# ADC_Arduino_Uno_Shield.net
KiCad netlist of a schematic drawn in EAGLE
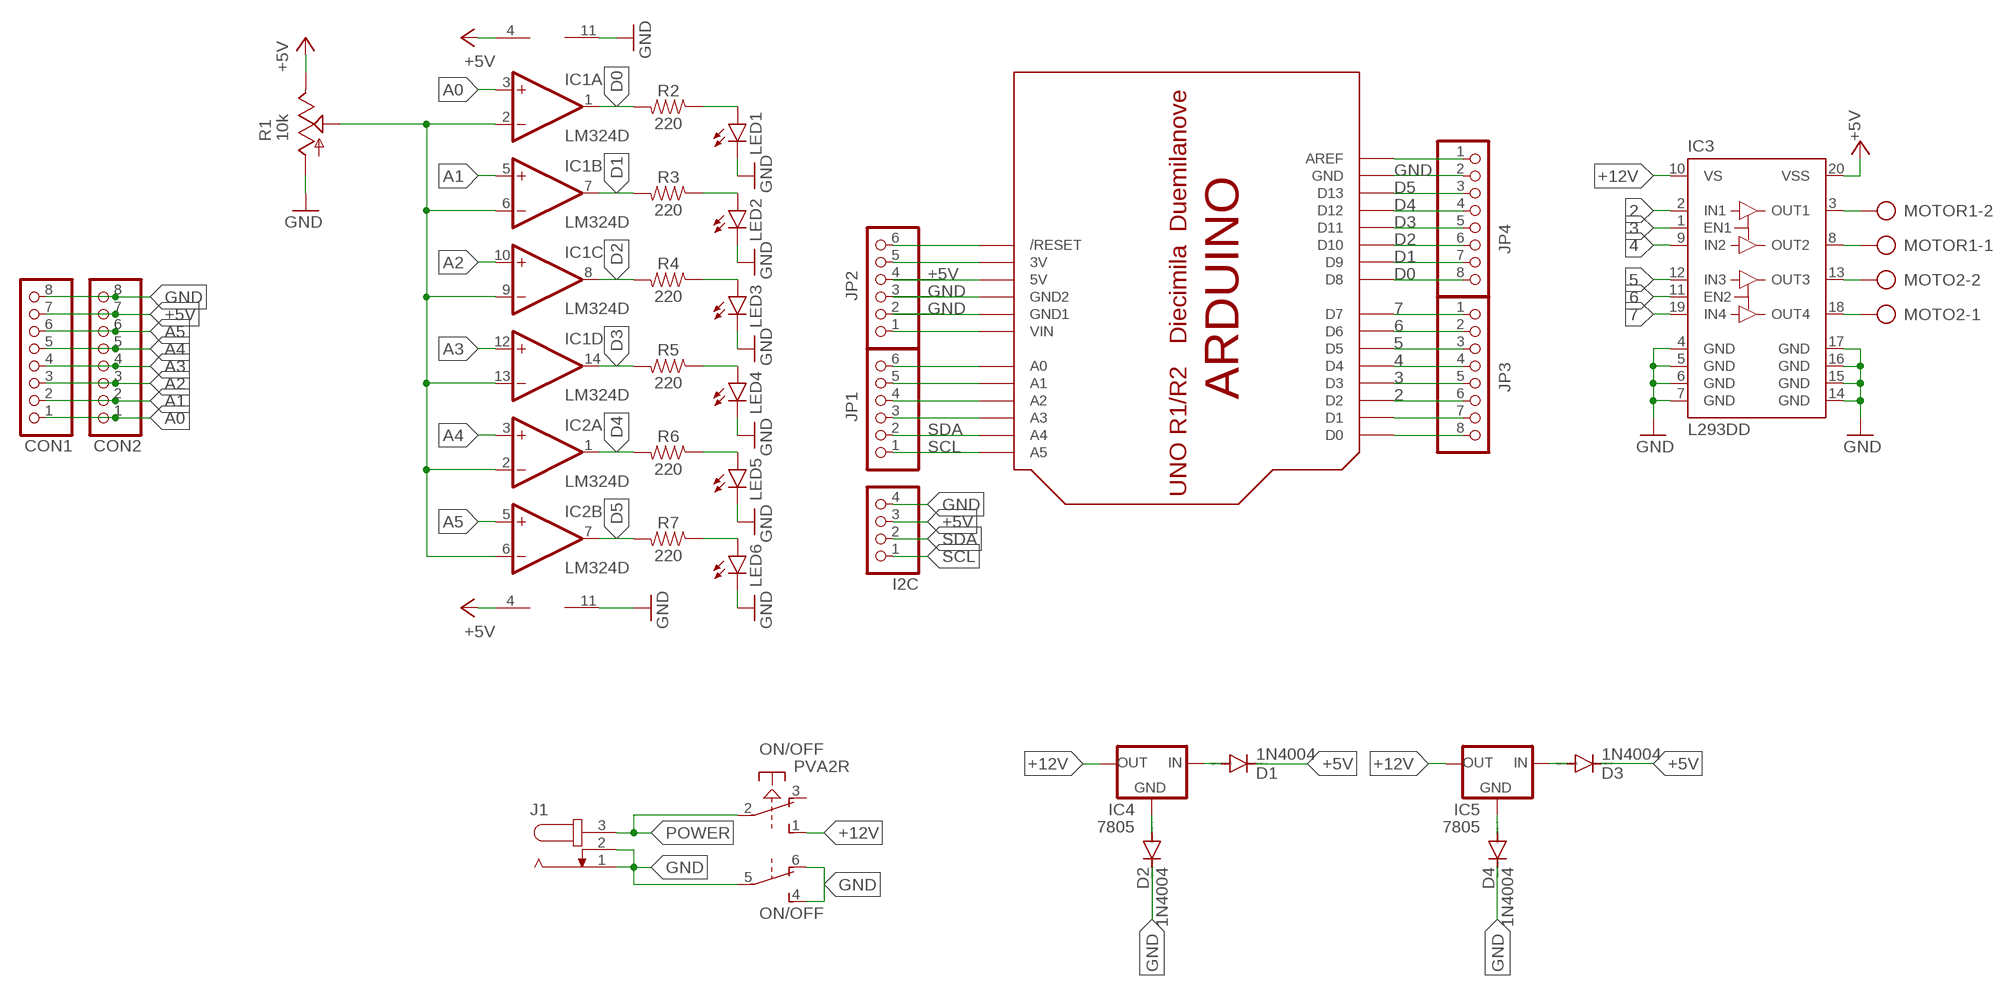
[diagram p0: schematic, sheet 1]

(export (version "E")
  (design (tool "Eeschema 10.0.6"))
  (components
    (comp (ref "CON1")
      (value "PINHD-1X8")
      (footprint "eagle-import:1X08")
      (libsource (lib "eagle-import") (part "PINHD-1X8"))
    )
    (comp (ref "CON2")
      (value "PINHD-1X8")
      (footprint "eagle-import:1X08")
      (libsource (lib "eagle-import") (part "PINHD-1X8"))
    )
    (comp (ref "D1")
      (value "1N4004")
      (footprint "eagle-import:DO41-10")
      (libsource (lib "eagle-import") (part "1N4004"))
    )
    (comp (ref "D2")
      (value "1N4004")
      (footprint "eagle-import:DO41-10")
      (libsource (lib "eagle-import") (part "1N4004"))
    )
    (comp (ref "D3")
      (value "1N4004")
      (footprint "eagle-import:DO41-10")
      (libsource (lib "eagle-import") (part "1N4004"))
    )
    (comp (ref "D4")
      (value "1N4004")
      (footprint "eagle-import:DO41-10")
      (libsource (lib "eagle-import") (part "1N4004"))
    )
    (comp (ref "I2C")
      (value "PINHD-1X4")
      (footprint "eagle-import:1X04")
      (libsource (lib "eagle-import") (part "PINHD-1X4"))
    )
    (comp (ref "IC1")
      (value "LM324D")
      (footprint "eagle-import:SO14")
      (libsource (lib "eagle-import") (part "LM324D"))
    )
    (comp (ref "IC2")
      (value "LM324D")
      (footprint "eagle-import:SO14")
      (libsource (lib "eagle-import") (part "LM324D"))
    )
    (comp (ref "IC3")
      (value "L293DD")
      (footprint "eagle-import:SO20")
      (libsource (lib "eagle-import") (part "L293DD"))
    )
    (comp (ref "IC4")
      (value "7805")
      (footprint "eagle-import:78XXS")
      (libsource (lib "eagle-import") (part "78XXS"))
    )
    (comp (ref "IC5")
      (value "7805")
      (footprint "eagle-import:78XXS")
      (libsource (lib "eagle-import") (part "78XXS"))
    )
    (comp (ref "J1")
      (value "JACK-PLUG0")
      (footprint "eagle-import:SPC4077")
      (libsource (lib "eagle-import") (part "JACK-PLUG0"))
    )
    (comp (ref "JP1")
      (value "PINHD-1X6")
      (footprint "eagle-import:1X06")
      (libsource (lib "eagle-import") (part "PINHD-1X6"))
    )
    (comp (ref "JP2")
      (value "PINHD-1X6")
      (footprint "eagle-import:1X06")
      (libsource (lib "eagle-import") (part "PINHD-1X6"))
    )
    (comp (ref "JP3")
      (value "PINHD-1X8")
      (footprint "eagle-import:1X08")
      (libsource (lib "eagle-import") (part "pinhead_325_PINHD-1X8"))
    )
    (comp (ref "JP4")
      (value "PINHD-1X8")
      (footprint "eagle-import:1X08")
      (libsource (lib "eagle-import") (part "pinhead_325_PINHD-1X8"))
    )
    (comp (ref "LED1")
      (value "LEDSML0805")
      (footprint "eagle-import:SML0805")
      (libsource (lib "eagle-import") (part "LEDSML0805"))
    )
    (comp (ref "LED2")
      (value "LEDSML0805")
      (footprint "eagle-import:SML0805")
      (libsource (lib "eagle-import") (part "LEDSML0805"))
    )
    (comp (ref "LED3")
      (value "LEDSML0805")
      (footprint "eagle-import:SML0805")
      (libsource (lib "eagle-import") (part "LEDSML0805"))
    )
    (comp (ref "LED4")
      (value "LEDSML0805")
      (footprint "eagle-import:SML0805")
      (libsource (lib "eagle-import") (part "LEDSML0805"))
    )
    (comp (ref "LED5")
      (value "LEDSML0805")
      (footprint "eagle-import:SML0805")
      (libsource (lib "eagle-import") (part "LEDSML0805"))
    )
    (comp (ref "LED6")
      (value "LEDSML0805")
      (footprint "eagle-import:SML0805")
      (libsource (lib "eagle-import") (part "LEDSML0805"))
    )
    (comp (ref "MOTO2")
      (value "AK500/2-H")
      (footprint "eagle-import:AK500_2-H")
      (libsource (lib "eagle-import") (part "AK500/2-H"))
    )
    (comp (ref "MOTOR1")
      (value "AK500/2-H")
      (footprint "eagle-import:AK500_2-H")
      (libsource (lib "eagle-import") (part "AK500/2-H"))
    )
    (comp (ref "ON/OFF")
      (value "PVA2R")
      (footprint "eagle-import:PVA2R")
      (libsource (lib "eagle-import") (part "PVA2R"))
    )
    (comp (ref "R1")
      (value "10k")
      (footprint "eagle-import:CA9V")
      (libsource (lib "eagle-import") (part "TRIM_US-CA9V"))
    )
    (comp (ref "R2")
      (value "220")
      (footprint "eagle-import:1206")
      (libsource (lib "eagle-import") (part "RESISTOR1206"))
    )
    (comp (ref "R3")
      (value "220")
      (footprint "eagle-import:1206")
      (libsource (lib "eagle-import") (part "RESISTOR1206"))
    )
    (comp (ref "R4")
      (value "220")
      (footprint "eagle-import:1206")
      (libsource (lib "eagle-import") (part "RESISTOR1206"))
    )
    (comp (ref "R5")
      (value "220")
      (footprint "eagle-import:1206")
      (libsource (lib "eagle-import") (part "RESISTOR1206"))
    )
    (comp (ref "R6")
      (value "220")
      (footprint "eagle-import:1206")
      (libsource (lib "eagle-import") (part "RESISTOR1206"))
    )
    (comp (ref "R7")
      (value "220")
      (footprint "eagle-import:1206")
      (libsource (lib "eagle-import") (part "RESISTOR1206"))
    )
    (comp (ref "U$2")
      (value "ARDUINO-NODIM")
      (footprint "eagle-import:ARDUINO-NODIM")
      (libsource (lib "eagle-import") (part "ARDUINO-NODIM"))
    )
  )
  (nets
    (net (code "1") (name "+5V") (class "Default")
      (node (ref "CON1") (pin "7") (pinfunction "7_7") (pintype "passive"))
      (node (ref "CON2") (pin "7") (pinfunction "7_7") (pintype "passive"))
      (node (ref "D1") (pin "C") (pinfunction "C_C") (pintype "passive"))
      (node (ref "D3") (pin "C") (pinfunction "C_C") (pintype "passive"))
      (node (ref "I2C") (pin "3") (pinfunction "3_3") (pintype "passive"))
      (node (ref "IC1") (pin "4") (pinfunction "V+_4") (pintype "power_in"))
      (node (ref "IC2") (pin "4") (pinfunction "V+_4") (pintype "power_in"))
      (node (ref "IC3") (pin "20") (pinfunction "VSS_20") (pintype "power_in"))
      (node (ref "JP2") (pin "4") (pinfunction "4_4") (pintype "passive"))
      (node (ref "R1") (pin "E") (pinfunction "E_E") (pintype "passive"))
      (node (ref "U$2") (pin "5V") (pinfunction "5V_5V") (pintype "power_in"))
    )
    (net (code "2") (name "+12V") (class "Default")
      (node (ref "IC3") (pin "10") (pinfunction "VS_10") (pintype "power_in"))
      (node (ref "IC4") (pin "OUT") (pinfunction "OUT_OUT") (pintype "passive"))
      (node (ref "IC5") (pin "OUT") (pinfunction "OUT_OUT") (pintype "passive"))
      (node (ref "ON/OFF") (pin "1") (pinfunction "S_1") (pintype "passive"))
    )
    (net (code "3") (name "2") (class "Default")
      (node (ref "IC3") (pin "2") (pinfunction "IN1_2") (pintype "input"))
      (node (ref "JP3") (pin "6") (pinfunction "6_6") (pintype "passive"))
      (node (ref "U$2") (pin "D2") (pinfunction "D2_D2") (pintype "bidirectional"))
    )
    (net (code "4") (name "3") (class "Default")
      (node (ref "IC3") (pin "1") (pinfunction "EN1_1") (pintype "input"))
      (node (ref "JP3") (pin "5") (pinfunction "5_5") (pintype "passive"))
      (node (ref "U$2") (pin "D3") (pinfunction "D3_D3") (pintype "bidirectional"))
    )
    (net (code "5") (name "4") (class "Default")
      (node (ref "IC3") (pin "9") (pinfunction "IN2_9") (pintype "input"))
      (node (ref "JP3") (pin "4") (pinfunction "4_4") (pintype "passive"))
      (node (ref "U$2") (pin "D4") (pinfunction "D4_D4") (pintype "bidirectional"))
    )
    (net (code "6") (name "5") (class "Default")
      (node (ref "IC3") (pin "12") (pinfunction "IN3_12") (pintype "input"))
      (node (ref "JP3") (pin "3") (pinfunction "3_3") (pintype "passive"))
      (node (ref "U$2") (pin "D5") (pinfunction "D5_D5") (pintype "bidirectional"))
    )
    (net (code "7") (name "6") (class "Default")
      (node (ref "IC3") (pin "11") (pinfunction "EN2_11") (pintype "input"))
      (node (ref "JP3") (pin "2") (pinfunction "2_2") (pintype "passive"))
      (node (ref "U$2") (pin "D6") (pinfunction "D6_D6") (pintype "bidirectional"))
    )
    (net (code "8") (name "7") (class "Default")
      (node (ref "IC3") (pin "19") (pinfunction "IN4_19") (pintype "input"))
      (node (ref "JP3") (pin "1") (pinfunction "1_1") (pintype "passive"))
      (node (ref "U$2") (pin "D7") (pinfunction "D7_D7") (pintype "bidirectional"))
    )
    (net (code "9") (name "A0") (class "Default")
      (node (ref "CON1") (pin "1") (pinfunction "1_1") (pintype "passive"))
      (node (ref "CON2") (pin "1") (pinfunction "1_1") (pintype "passive"))
      (node (ref "IC1") (pin "3") (pinfunction "+IN_3") (pintype "input"))
    )
    (net (code "10") (name "A1") (class "Default")
      (node (ref "CON1") (pin "2") (pinfunction "2_2") (pintype "passive"))
      (node (ref "CON2") (pin "2") (pinfunction "2_2") (pintype "passive"))
      (node (ref "IC1") (pin "5") (pinfunction "+IN_5") (pintype "input"))
    )
    (net (code "11") (name "A2") (class "Default")
      (node (ref "CON1") (pin "3") (pinfunction "3_3") (pintype "passive"))
      (node (ref "CON2") (pin "3") (pinfunction "3_3") (pintype "passive"))
      (node (ref "IC1") (pin "10") (pinfunction "+IN_10") (pintype "input"))
    )
    (net (code "12") (name "A3") (class "Default")
      (node (ref "CON1") (pin "4") (pinfunction "4_4") (pintype "passive"))
      (node (ref "CON2") (pin "4") (pinfunction "4_4") (pintype "passive"))
      (node (ref "IC1") (pin "12") (pinfunction "+IN_12") (pintype "input"))
    )
    (net (code "13") (name "A4") (class "Default")
      (node (ref "CON1") (pin "5") (pinfunction "5_5") (pintype "passive"))
      (node (ref "CON2") (pin "5") (pinfunction "5_5") (pintype "passive"))
      (node (ref "IC2") (pin "3") (pinfunction "+IN_3") (pintype "input"))
    )
    (net (code "14") (name "A5") (class "Default")
      (node (ref "CON1") (pin "6") (pinfunction "6_6") (pintype "passive"))
      (node (ref "CON2") (pin "6") (pinfunction "6_6") (pintype "passive"))
      (node (ref "IC2") (pin "5") (pinfunction "+IN_5") (pintype "input"))
    )
    (net (code "15") (name "D0") (class "Default")
      (node (ref "IC1") (pin "1") (pinfunction "OUT_1") (pintype "output"))
      (node (ref "JP4") (pin "8") (pinfunction "8_8") (pintype "passive"))
      (node (ref "R2") (pin "2") (pinfunction "2_2") (pintype "passive"))
      (node (ref "U$2") (pin "D8") (pinfunction "D8_D8") (pintype "bidirectional"))
    )
    (net (code "16") (name "D1") (class "Default")
      (node (ref "IC1") (pin "7") (pinfunction "OUT_7") (pintype "output"))
      (node (ref "JP4") (pin "7") (pinfunction "7_7") (pintype "passive"))
      (node (ref "R3") (pin "2") (pinfunction "2_2") (pintype "passive"))
      (node (ref "U$2") (pin "D9") (pinfunction "D9_D9") (pintype "bidirectional"))
    )
    (net (code "17") (name "D2") (class "Default")
      (node (ref "IC1") (pin "8") (pinfunction "OUT_8") (pintype "output"))
      (node (ref "JP4") (pin "6") (pinfunction "6_6") (pintype "passive"))
      (node (ref "R4") (pin "2") (pinfunction "2_2") (pintype "passive"))
      (node (ref "U$2") (pin "D10") (pinfunction "D10_D10") (pintype "bidirectional"))
    )
    (net (code "18") (name "D3") (class "Default")
      (node (ref "IC1") (pin "14") (pinfunction "OUT_14") (pintype "output"))
      (node (ref "JP4") (pin "5") (pinfunction "5_5") (pintype "passive"))
      (node (ref "R5") (pin "2") (pinfunction "2_2") (pintype "passive"))
      (node (ref "U$2") (pin "D11") (pinfunction "D11_D11") (pintype "bidirectional"))
    )
    (net (code "19") (name "D4") (class "Default")
      (node (ref "IC2") (pin "1") (pinfunction "OUT_1") (pintype "output"))
      (node (ref "JP4") (pin "4") (pinfunction "4_4") (pintype "passive"))
      (node (ref "R6") (pin "2") (pinfunction "2_2") (pintype "passive"))
      (node (ref "U$2") (pin "D12") (pinfunction "D12_D12") (pintype "bidirectional"))
    )
    (net (code "20") (name "D5") (class "Default")
      (node (ref "IC2") (pin "7") (pinfunction "OUT_7") (pintype "output"))
      (node (ref "JP4") (pin "3") (pinfunction "3_3") (pintype "passive"))
      (node (ref "R7") (pin "2") (pinfunction "2_2") (pintype "passive"))
      (node (ref "U$2") (pin "D13") (pinfunction "D13_D13") (pintype "bidirectional"))
    )
    (net (code "21") (name "GND") (class "Default")
      (node (ref "CON1") (pin "8") (pinfunction "8_8") (pintype "passive"))
      (node (ref "CON2") (pin "8") (pinfunction "8_8") (pintype "passive"))
      (node (ref "D2") (pin "C") (pinfunction "C_C") (pintype "passive"))
      (node (ref "D4") (pin "C") (pinfunction "C_C") (pintype "passive"))
      (node (ref "I2C") (pin "4") (pinfunction "4_4") (pintype "passive"))
      (node (ref "IC1") (pin "11") (pinfunction "V-_11") (pintype "power_in"))
      (node (ref "IC2") (pin "11") (pinfunction "V-_11") (pintype "power_in"))
      (node (ref "IC3") (pin "14") (pinfunction "GND_14") (pintype "power_in"))
      (node (ref "IC3") (pin "15") (pinfunction "GND_15") (pintype "power_in"))
      (node (ref "IC3") (pin "16") (pinfunction "GND_16") (pintype "power_in"))
      (node (ref "IC3") (pin "17") (pinfunction "GND_17") (pintype "power_in"))
      (node (ref "IC3") (pin "4") (pinfunction "GND_4") (pintype "power_in"))
      (node (ref "IC3") (pin "5") (pinfunction "GND_5") (pintype "power_in"))
      (node (ref "IC3") (pin "6") (pinfunction "GND_6") (pintype "power_in"))
      (node (ref "IC3") (pin "7") (pinfunction "GND_7") (pintype "power_in"))
      (node (ref "J1") (pin "1") (pinfunction "1_1") (pintype "passive"))
      (node (ref "J1") (pin "2") (pinfunction "2_2") (pintype "passive"))
      (node (ref "JP2") (pin "2") (pinfunction "2_2") (pintype "passive"))
      (node (ref "JP2") (pin "3") (pinfunction "3_3") (pintype "passive"))
      (node (ref "JP4") (pin "2") (pinfunction "2_2") (pintype "passive"))
      (node (ref "LED1") (pin "C") (pinfunction "C_C") (pintype "passive"))
      (node (ref "LED2") (pin "C") (pinfunction "C_C") (pintype "passive"))
      (node (ref "LED3") (pin "C") (pinfunction "C_C") (pintype "passive"))
      (node (ref "LED4") (pin "C") (pinfunction "C_C") (pintype "passive"))
      (node (ref "LED5") (pin "C") (pinfunction "C_C") (pintype "passive"))
      (node (ref "LED6") (pin "C") (pinfunction "C_C") (pintype "passive"))
      (node (ref "ON/OFF") (pin "4") (pinfunction "S_4") (pintype "passive"))
      (node (ref "ON/OFF") (pin "5") (pinfunction "P_5") (pintype "passive"))
      (node (ref "ON/OFF") (pin "6") (pinfunction "O_6") (pintype "passive"))
      (node (ref "R1") (pin "A") (pinfunction "A_A") (pintype "passive"))
      (node (ref "U$2") (pin "GND") (pinfunction "GND_GND") (pintype "power_in"))
      (node (ref "U$2") (pin "GND1") (pinfunction "GND1_GND1") (pintype "power_in"))
      (node (ref "U$2") (pin "GND2") (pinfunction "GND2_GND2") (pintype "power_in"))
    )
    (net (code "22") (name "Net-(D1-PadA)") (class "Default")
      (node (ref "D1") (pin "A") (pinfunction "A_A") (pintype "passive"))
      (node (ref "IC4") (pin "IN") (pinfunction "IN_IN") (pintype "input"))
    )
    (net (code "23") (name "Net-(D2-PadA)") (class "Default")
      (node (ref "D2") (pin "A") (pinfunction "A_A") (pintype "passive"))
      (node (ref "IC4") (pin "GND") (pinfunction "GND_GND") (pintype "input"))
    )
    (net (code "24") (name "Net-(D3-PadA)") (class "Default")
      (node (ref "D3") (pin "A") (pinfunction "A_A") (pintype "passive"))
      (node (ref "IC5") (pin "IN") (pinfunction "IN_IN") (pintype "input"))
    )
    (net (code "25") (name "Net-(D4-PadA)") (class "Default")
      (node (ref "D4") (pin "A") (pinfunction "A_A") (pintype "passive"))
      (node (ref "IC5") (pin "GND") (pinfunction "GND_GND") (pintype "input"))
    )
    (net (code "26") (name "Net-(IC1A--IN)") (class "Default")
      (node (ref "IC1") (pin "13") (pinfunction "-IN_13") (pintype "input"))
      (node (ref "IC1") (pin "2") (pinfunction "-IN_2") (pintype "input"))
      (node (ref "IC1") (pin "6") (pinfunction "-IN_6") (pintype "input"))
      (node (ref "IC1") (pin "9") (pinfunction "-IN_9") (pintype "input"))
      (node (ref "IC2") (pin "2") (pinfunction "-IN_2") (pintype "input"))
      (node (ref "IC2") (pin "6") (pinfunction "-IN_6") (pintype "input"))
      (node (ref "R1") (pin "S") (pinfunction "S_S") (pintype "passive"))
    )
    (net (code "27") (name "Net-(IC3-OUT1)") (class "Default")
      (node (ref "IC3") (pin "3") (pinfunction "OUT1_3") (pintype "output"))
      (node (ref "MOTOR1") (pin "2") (pinfunction "KL_2") (pintype "passive"))
    )
    (net (code "28") (name "Net-(IC3-OUT2)") (class "Default")
      (node (ref "IC3") (pin "8") (pinfunction "OUT2_8") (pintype "output"))
      (node (ref "MOTOR1") (pin "1") (pinfunction "KL_1") (pintype "passive"))
    )
    (net (code "29") (name "Net-(IC3-OUT3)") (class "Default")
      (node (ref "IC3") (pin "13") (pinfunction "OUT3_13") (pintype "output"))
      (node (ref "MOTO2") (pin "2") (pinfunction "KL_2") (pintype "passive"))
    )
    (net (code "30") (name "Net-(IC3-OUT4)") (class "Default")
      (node (ref "IC3") (pin "18") (pinfunction "OUT4_18") (pintype "output"))
      (node (ref "MOTO2") (pin "1") (pinfunction "KL_1") (pintype "passive"))
    )
    (net (code "31") (name "Net-(JP1-Pad3)") (class "Default")
      (node (ref "JP1") (pin "3") (pinfunction "3_3") (pintype "passive"))
      (node (ref "U$2") (pin "A3") (pinfunction "A3_A3") (pintype "bidirectional"))
    )
    (net (code "32") (name "Net-(JP1-Pad4)") (class "Default")
      (node (ref "JP1") (pin "4") (pinfunction "4_4") (pintype "passive"))
      (node (ref "U$2") (pin "A2") (pinfunction "A2_A2") (pintype "bidirectional"))
    )
    (net (code "33") (name "Net-(JP1-Pad5)") (class "Default")
      (node (ref "JP1") (pin "5") (pinfunction "5_5") (pintype "passive"))
      (node (ref "U$2") (pin "A1") (pinfunction "A1_A1") (pintype "bidirectional"))
    )
    (net (code "34") (name "Net-(JP1-Pad6)") (class "Default")
      (node (ref "JP1") (pin "6") (pinfunction "6_6") (pintype "passive"))
      (node (ref "U$2") (pin "A0") (pinfunction "A0_A0") (pintype "bidirectional"))
    )
    (net (code "35") (name "Net-(JP2-Pad1)") (class "Default")
      (node (ref "JP2") (pin "1") (pinfunction "1_1") (pintype "passive"))
      (node (ref "U$2") (pin "VIN") (pinfunction "VIN_VIN") (pintype "power_in"))
    )
    (net (code "36") (name "Net-(JP2-Pad5)") (class "Default")
      (node (ref "JP2") (pin "5") (pinfunction "5_5") (pintype "passive"))
      (node (ref "U$2") (pin "3V") (pinfunction "3V_3V") (pintype "power_in"))
    )
    (net (code "37") (name "Net-(JP3-Pad7)") (class "Default")
      (node (ref "JP3") (pin "7") (pinfunction "7_7") (pintype "passive"))
      (node (ref "U$2") (pin "D1") (pinfunction "D1_D1") (pintype "bidirectional"))
    )
    (net (code "38") (name "Net-(JP3-Pad8)") (class "Default")
      (node (ref "JP3") (pin "8") (pinfunction "8_8") (pintype "passive"))
      (node (ref "U$2") (pin "D0") (pinfunction "D0_D0") (pintype "bidirectional"))
    )
    (net (code "39") (name "Net-(JP4-Pad1)") (class "Default")
      (node (ref "JP4") (pin "1") (pinfunction "1_1") (pintype "passive"))
      (node (ref "U$2") (pin "AREF") (pinfunction "AREF_AREF") (pintype "bidirectional"))
    )
    (net (code "40") (name "Net-(LED1-PadA)") (class "Default")
      (node (ref "LED1") (pin "A") (pinfunction "A_A") (pintype "passive"))
      (node (ref "R2") (pin "1") (pinfunction "1_1") (pintype "passive"))
    )
    (net (code "41") (name "Net-(LED2-PadA)") (class "Default")
      (node (ref "LED2") (pin "A") (pinfunction "A_A") (pintype "passive"))
      (node (ref "R3") (pin "1") (pinfunction "1_1") (pintype "passive"))
    )
    (net (code "42") (name "Net-(LED3-PadA)") (class "Default")
      (node (ref "LED3") (pin "A") (pinfunction "A_A") (pintype "passive"))
      (node (ref "R4") (pin "1") (pinfunction "1_1") (pintype "passive"))
    )
    (net (code "43") (name "Net-(LED4-PadA)") (class "Default")
      (node (ref "LED4") (pin "A") (pinfunction "A_A") (pintype "passive"))
      (node (ref "R5") (pin "1") (pinfunction "1_1") (pintype "passive"))
    )
    (net (code "44") (name "Net-(LED5-PadA)") (class "Default")
      (node (ref "LED5") (pin "A") (pinfunction "A_A") (pintype "passive"))
      (node (ref "R6") (pin "1") (pinfunction "1_1") (pintype "passive"))
    )
    (net (code "45") (name "Net-(LED6-PadA)") (class "Default")
      (node (ref "LED6") (pin "A") (pinfunction "A_A") (pintype "passive"))
      (node (ref "R7") (pin "1") (pinfunction "1_1") (pintype "passive"))
    )
    (net (code "46") (name "Net-(U$2-{slash}RESET)") (class "Default")
      (node (ref "JP2") (pin "6") (pinfunction "6_6") (pintype "passive"))
      (node (ref "U$2") (pin "RESET") (pinfunction "/RESET_RESET") (pintype "bidirectional"))
    )
    (net (code "47") (name "POWER") (class "Default")
      (node (ref "J1") (pin "3") (pinfunction "3_3") (pintype "passive"))
      (node (ref "ON/OFF") (pin "2") (pinfunction "P_2") (pintype "passive"))
    )
    (net (code "48") (name "SCL") (class "Default")
      (node (ref "I2C") (pin "1") (pinfunction "1_1") (pintype "passive"))
      (node (ref "JP1") (pin "1") (pinfunction "1_1") (pintype "passive"))
      (node (ref "U$2") (pin "A5") (pinfunction "A5_A5") (pintype "bidirectional"))
    )
    (net (code "49") (name "SDA") (class "Default")
      (node (ref "I2C") (pin "2") (pinfunction "2_2") (pintype "passive"))
      (node (ref "JP1") (pin "2") (pinfunction "2_2") (pintype "passive"))
      (node (ref "U$2") (pin "A4") (pinfunction "A4_A4") (pintype "bidirectional"))
    )
    (net (code "50") (name "unconnected-(ON/OFFA-O-Pad3)") (class "Default")
      (node (ref "ON/OFF") (pin "3") (pinfunction "O_3") (pintype "passive"))
    )
  )
)
